# Patch-Prop.net
KiCad netlist of a schematic drawn in EAGLE
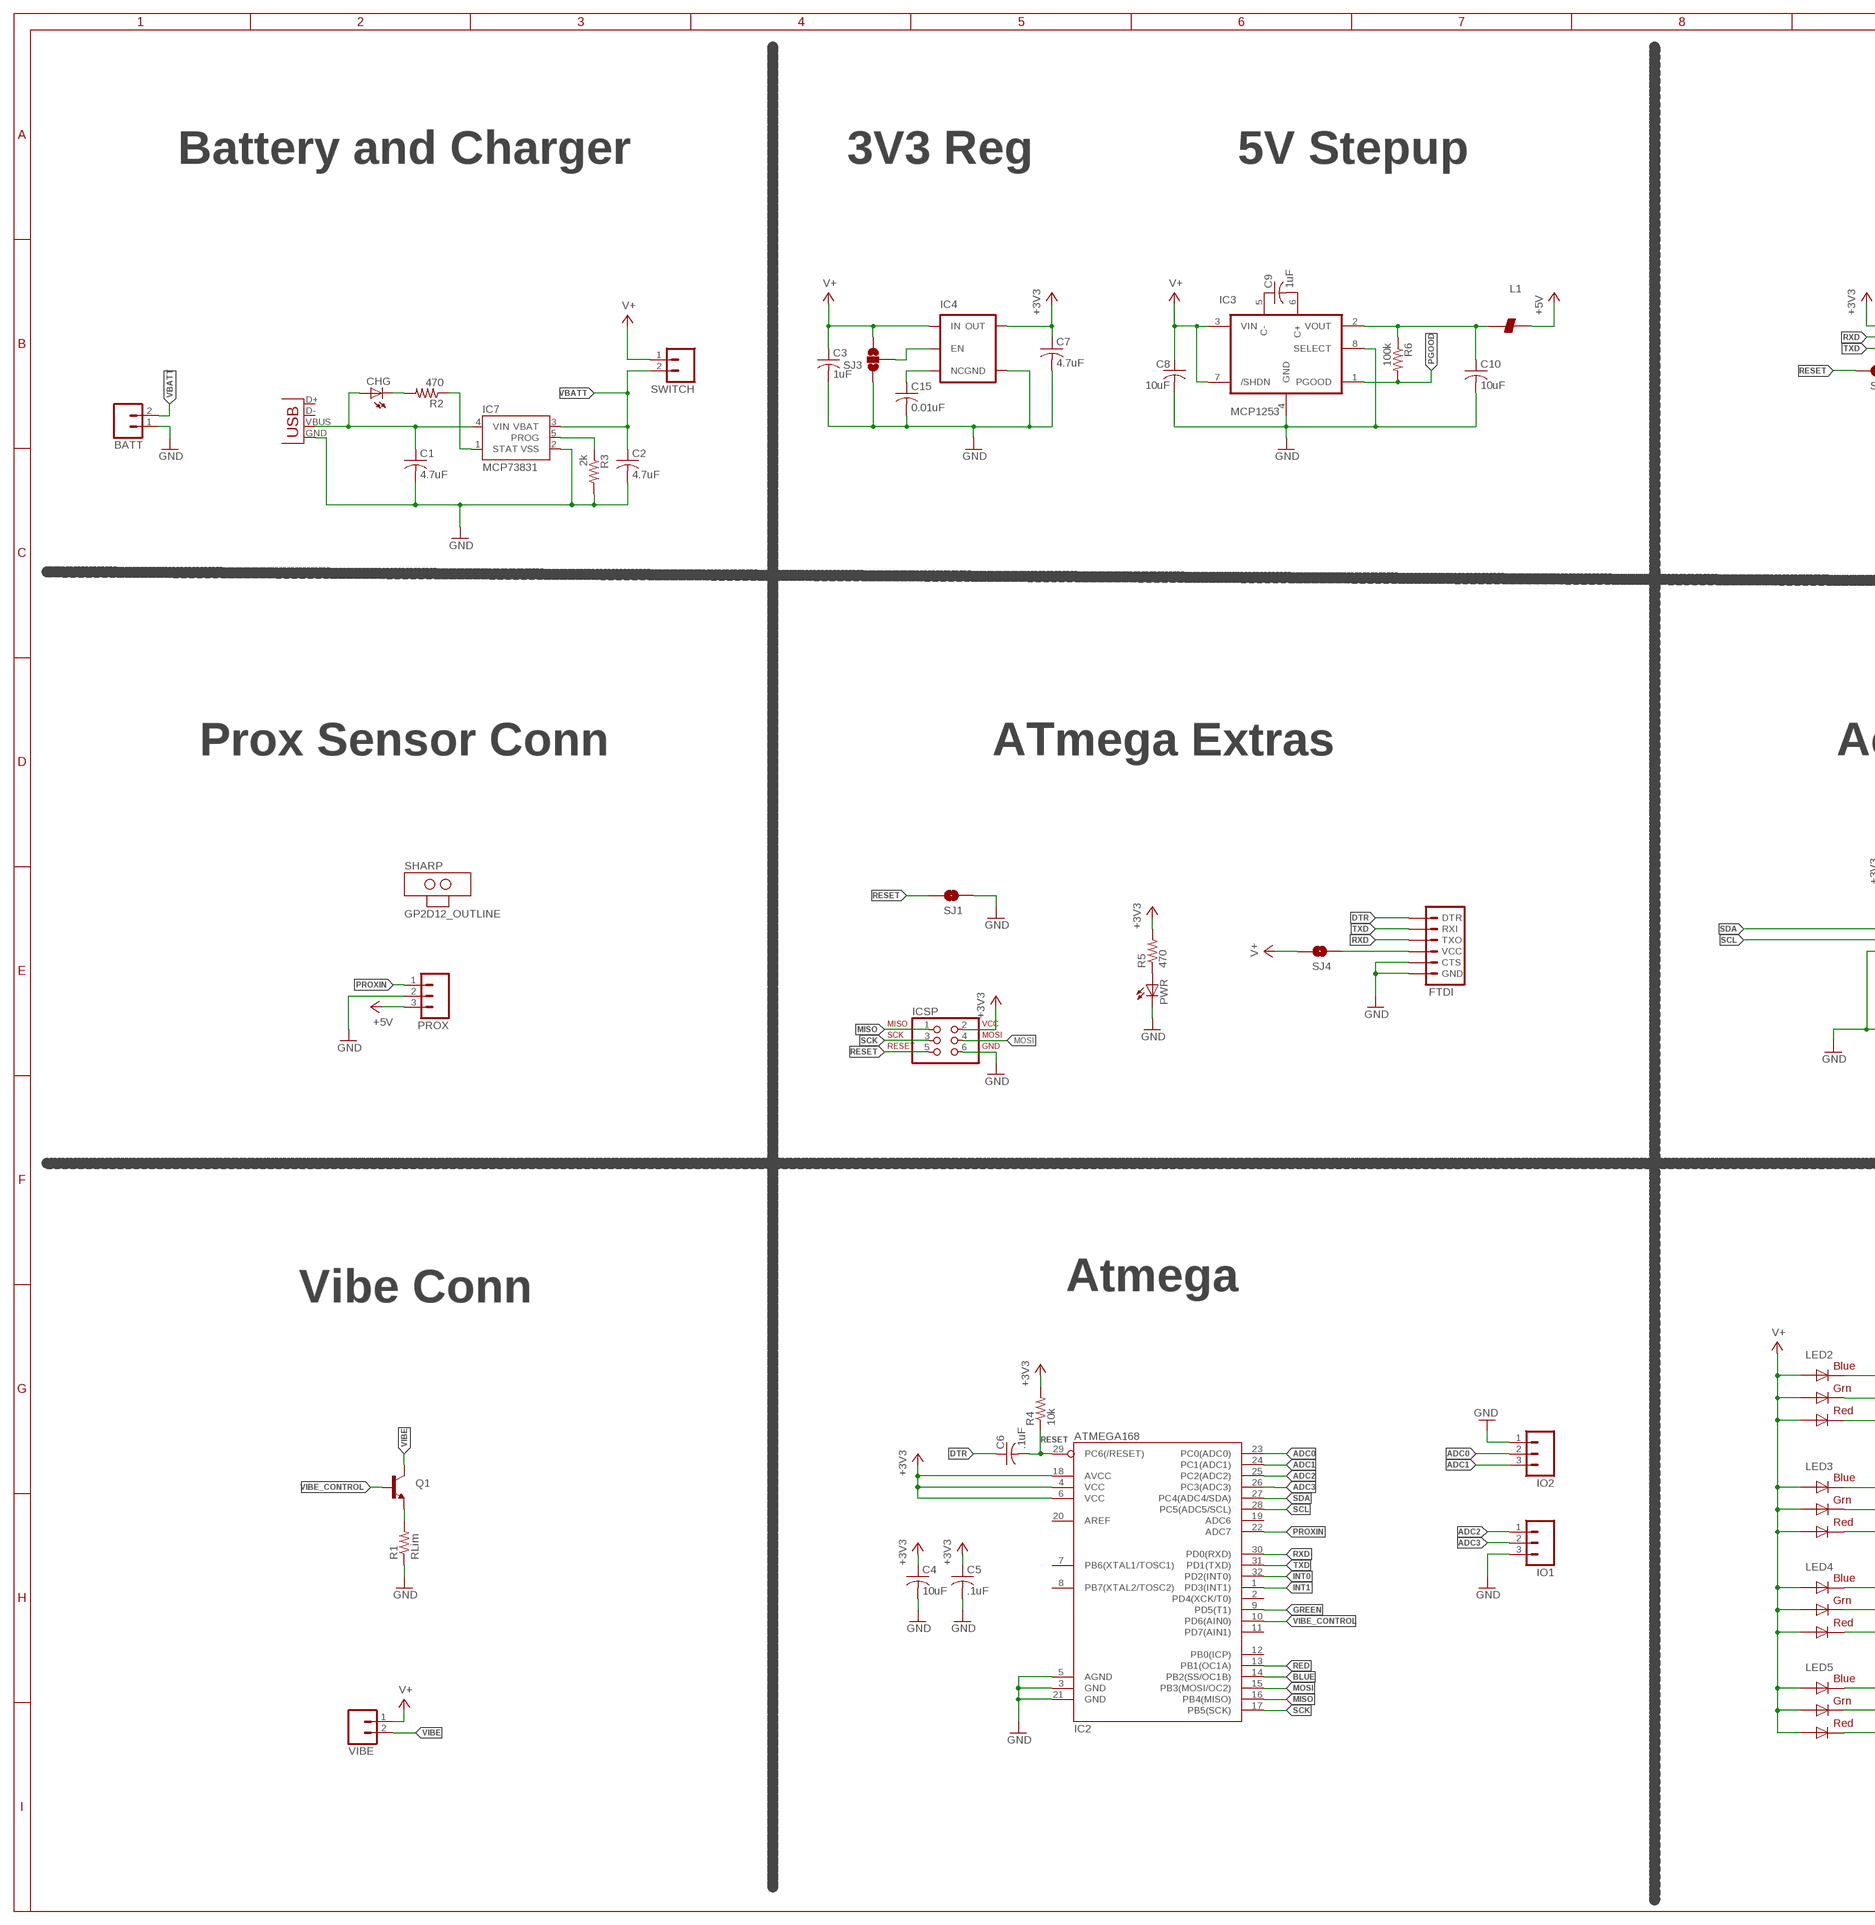
[diagram p0: schematic, sheet 1, part 1 of 2]
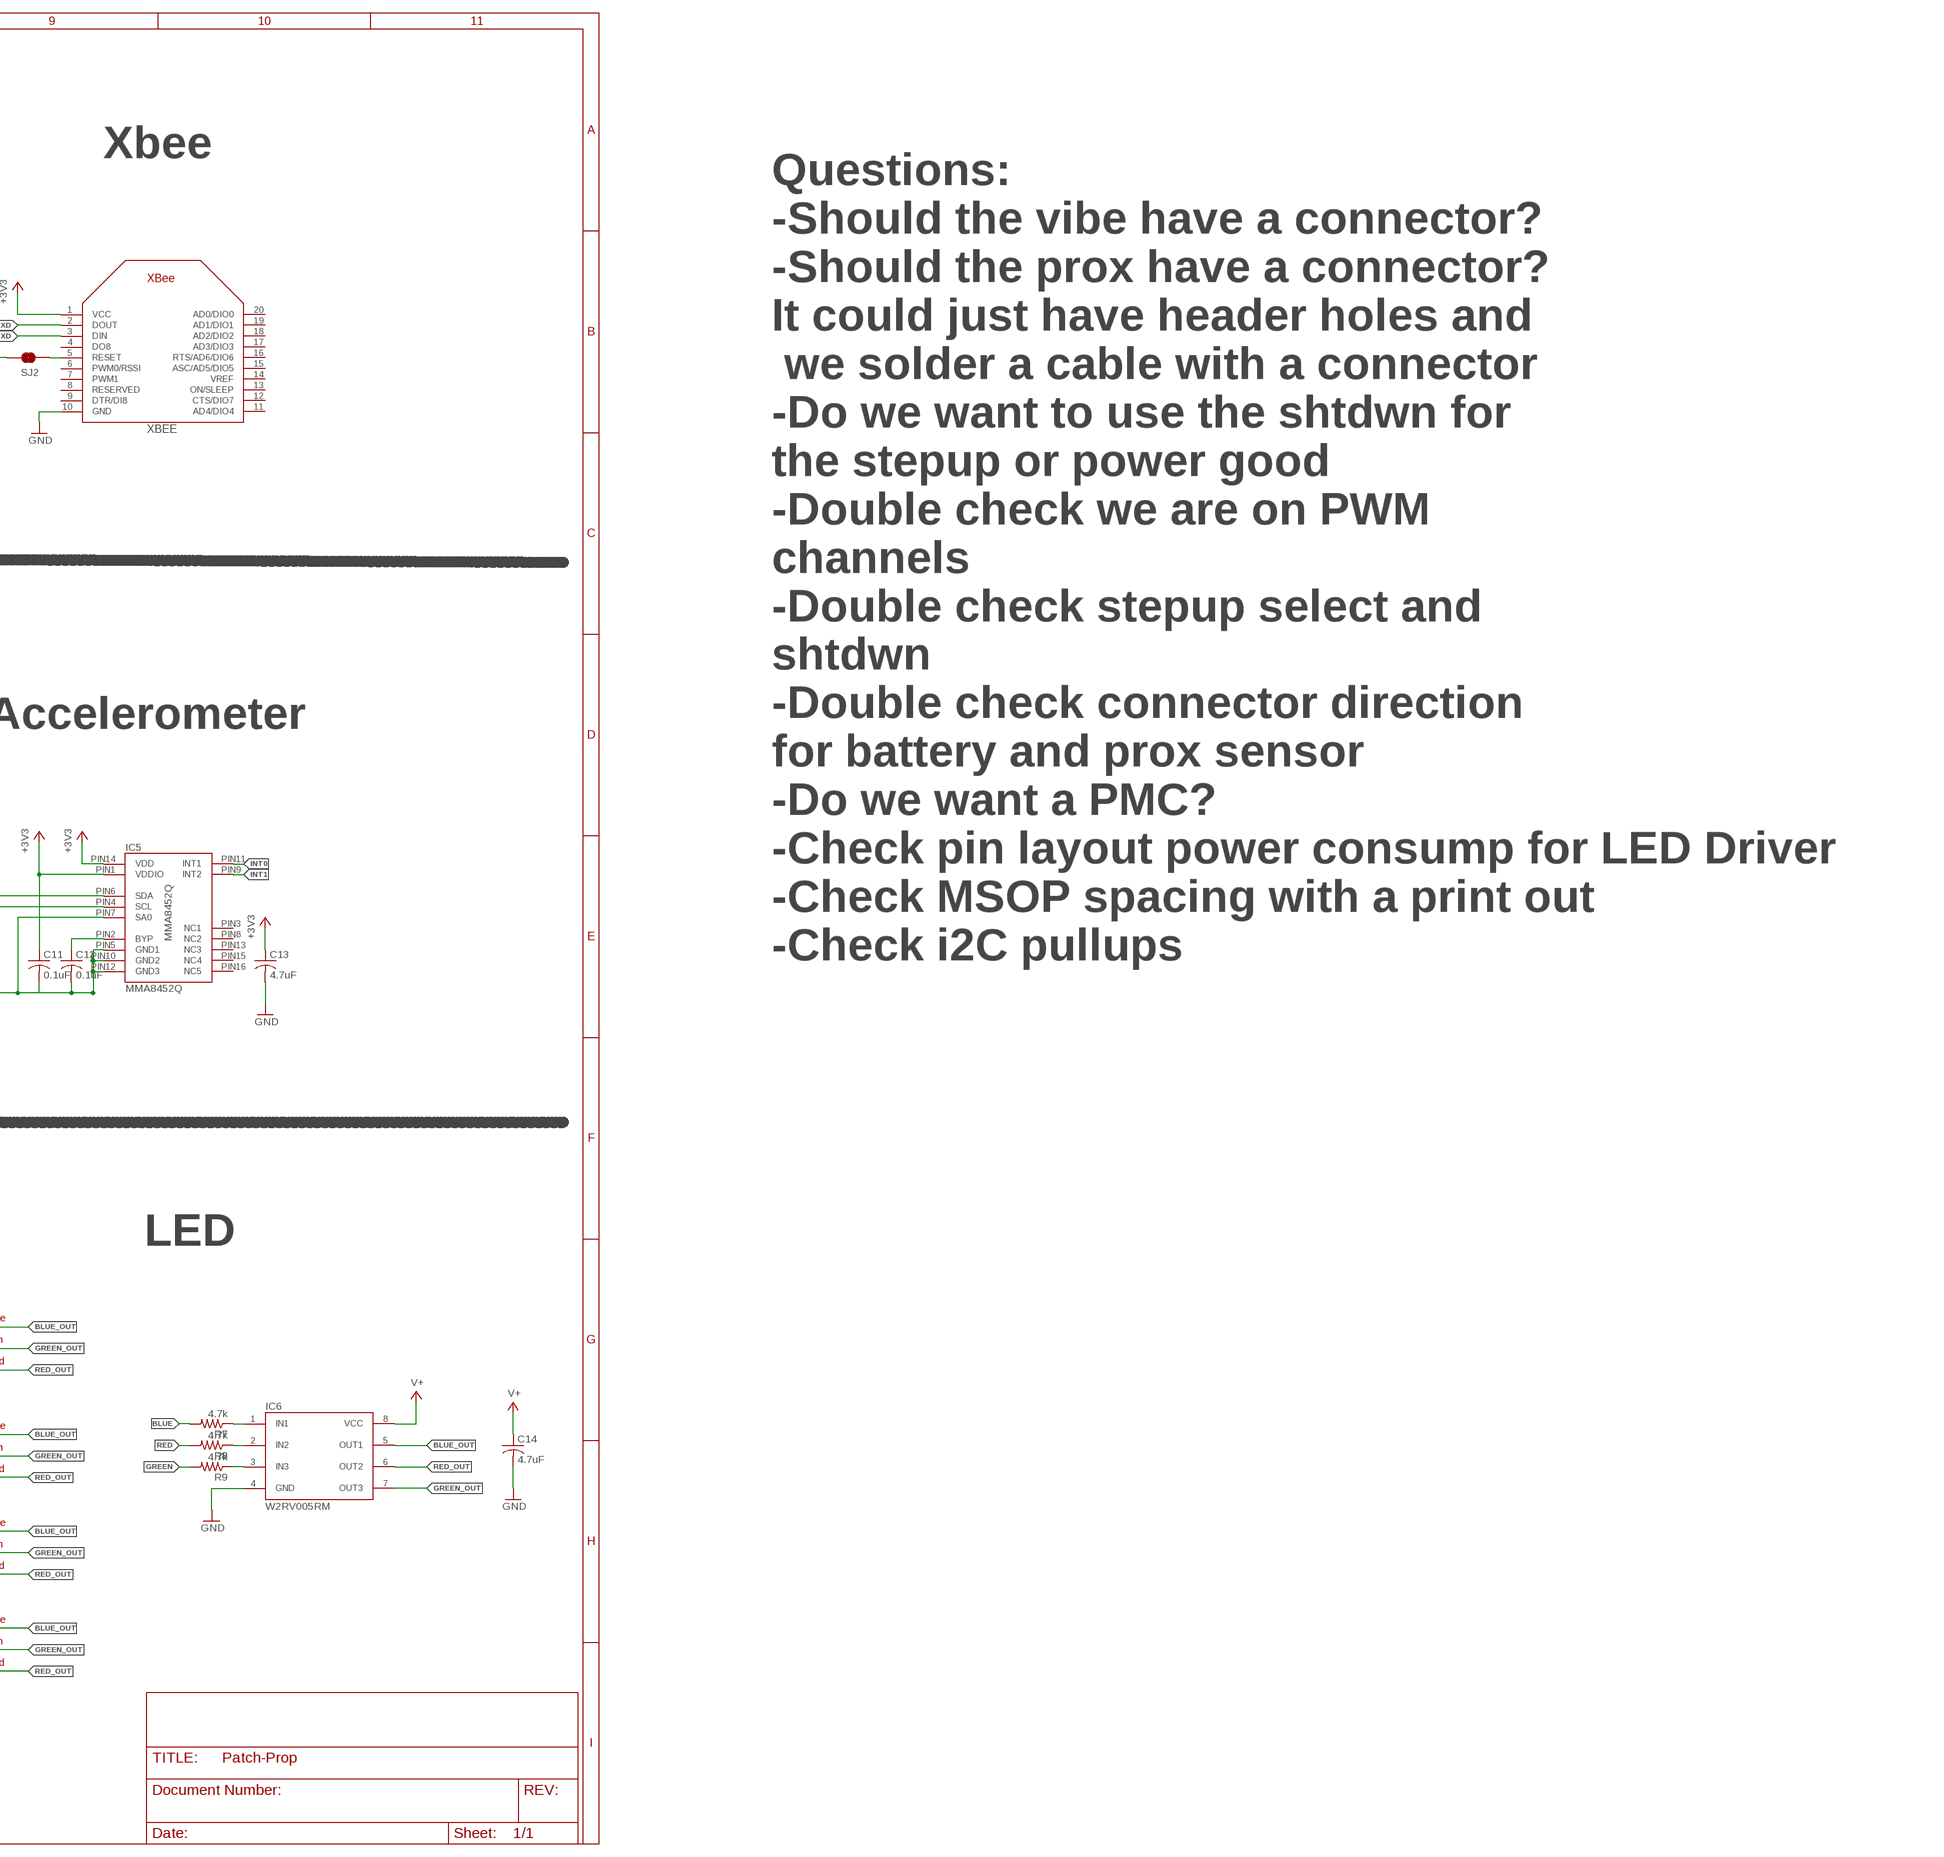
[diagram p1: schematic, sheet 1, part 2 of 2]

(export (version "E")
  (design (tool "Eeschema 10.0.6"))
  (components
    (comp (ref "BATT")
      (value "M02-JST-2MM-SMT")
      (footprint "eagle-import:JST-2-SMD")
      (libsource (lib "eagle-import") (part "SparkFun-Connectors_M02-JST-2MM-SMT"))
    )
    (comp (ref "C1")
      (value "4.7uF")
      (footprint "eagle-import:C0603")
      (libsource (lib "eagle-import") (part "C-USC0603"))
    )
    (comp (ref "C2")
      (value "4.7uF")
      (footprint "eagle-import:C0603")
      (libsource (lib "eagle-import") (part "C-USC0603"))
    )
    (comp (ref "C3")
      (value "1uF")
      (footprint "eagle-import:C0603")
      (libsource (lib "eagle-import") (part "C-USC0603"))
    )
    (comp (ref "C4")
      (value "10uF")
      (footprint "eagle-import:C0603")
      (libsource (lib "eagle-import") (part "C-USC0603"))
    )
    (comp (ref "C5")
      (value ".1uF")
      (footprint "eagle-import:C0603")
      (libsource (lib "eagle-import") (part "C-USC0603"))
    )
    (comp (ref "C6")
      (value ".1uF")
      (footprint "eagle-import:C0603")
      (libsource (lib "eagle-import") (part "C-USC0603"))
    )
    (comp (ref "C7")
      (value "4.7uF")
      (footprint "eagle-import:C0603")
      (libsource (lib "eagle-import") (part "C-USC0603"))
    )
    (comp (ref "C8")
      (value "10uF")
      (footprint "eagle-import:C0603")
      (libsource (lib "eagle-import") (part "C-USC0603"))
    )
    (comp (ref "C9")
      (value "1uF")
      (footprint "eagle-import:C0603")
      (libsource (lib "eagle-import") (part "C-USC0603"))
    )
    (comp (ref "C10")
      (value "10uF")
      (footprint "eagle-import:C0603")
      (libsource (lib "eagle-import") (part "C-USC0603"))
    )
    (comp (ref "C11")
      (value "0.1uF")
      (footprint "eagle-import:C0603")
      (libsource (lib "eagle-import") (part "C-USC0603"))
    )
    (comp (ref "C12")
      (value "0.1uF")
      (footprint "eagle-import:C0603")
      (libsource (lib "eagle-import") (part "C-USC0603"))
    )
    (comp (ref "C13")
      (value "4.7uF")
      (footprint "eagle-import:C0603")
      (libsource (lib "eagle-import") (part "C-USC0603"))
    )
    (comp (ref "C14")
      (value "4.7uF")
      (footprint "eagle-import:C0603")
      (libsource (lib "eagle-import") (part "C-USC0603"))
    )
    (comp (ref "C15")
      (value "0.01uF")
      (footprint "eagle-import:C0603")
      (libsource (lib "eagle-import") (part "C-USC0603"))
    )
    (comp (ref "CHG")
      (value "LEDCHIPLED_0805")
      (footprint "eagle-import:CHIPLED_0805")
      (libsource (lib "eagle-import") (part "LEDCHIPLED_0805"))
    )
    (comp (ref "FTDI")
      (value "ARDUINO_SERIAL_PROGRAMPTH")
      (footprint "eagle-import:1X06")
      (libsource (lib "eagle-import") (part "ARDUINO_SERIAL_PROGRAMPTH"))
    )
    (comp (ref "IC2")
      (value "ATMEGA168")
      (footprint "eagle-import:TQFP32-08")
      (libsource (lib "eagle-import") (part "ATMEGA168"))
    )
    (comp (ref "IC3")
      (value "MCP1253")
      (footprint "eagle-import:MSOP8")
      (libsource (lib "eagle-import") (part "MCP1253"))
    )
    (comp (ref "IC4")
      (value "V_REG_TPS76433SOT23-5")
      (footprint "eagle-import:SOT23-5")
      (libsource (lib "eagle-import") (part "V_REG_TPS76433SOT23-5"))
    )
    (comp (ref "IC5")
      (value "MMA8452Q")
      (footprint "eagle-import:QFN-16")
      (libsource (lib "eagle-import") (part "MMA8452Q"))
    )
    (comp (ref "IC6")
      (value "W2RV005RM")
      (footprint "eagle-import:MSOP8")
      (libsource (lib "eagle-import") (part "W2RV005RM"))
    )
    (comp (ref "IC7")
      (value "MCP73831")
      (footprint "eagle-import:SOT23-5")
      (libsource (lib "eagle-import") (part "MCP73831SMD"))
    )
    (comp (ref "ICSP")
      (value "ISP-AVR910SMD")
      (footprint "eagle-import:2X03_BORDER")
      (libsource (lib "eagle-import") (part "ISP-AVR910SMD"))
    )
    (comp (ref "IO1")
      (value "M03PTH")
      (footprint "eagle-import:1X03")
      (libsource (lib "eagle-import") (part "M03PTH"))
    )
    (comp (ref "IO2")
      (value "M03PTH")
      (footprint "eagle-import:1X03")
      (libsource (lib "eagle-import") (part "M03PTH"))
    )
    (comp (ref "L1")
      (value "BEAD-0805")
      (footprint "eagle-import:0805")
      (libsource (lib "eagle-import") (part "BEAD-0805"))
    )
    (comp (ref "LED2")
      (value "RGBLED5050")
      (footprint "eagle-import:RGBLED5050")
      (libsource (lib "eagle-import") (part "RGBLED5050"))
    )
    (comp (ref "LED3")
      (value "RGBLED5050")
      (footprint "eagle-import:RGBLED5050")
      (libsource (lib "eagle-import") (part "RGBLED5050"))
    )
    (comp (ref "LED4")
      (value "RGBLED5050")
      (footprint "eagle-import:RGBLED5050")
      (libsource (lib "eagle-import") (part "RGBLED5050"))
    )
    (comp (ref "LED5")
      (value "RGBLED5050")
      (footprint "eagle-import:RGBLED5050")
      (libsource (lib "eagle-import") (part "RGBLED5050"))
    )
    (comp (ref "PROX")
      (value "M03PTH")
      (footprint "eagle-import:1X03")
      (libsource (lib "eagle-import") (part "SparkFun-Connectors_M03PTH"))
    )
    (comp (ref "PWR")
      (value "LEDCHIPLED_0805")
      (footprint "eagle-import:CHIPLED_0805")
      (libsource (lib "eagle-import") (part "LEDCHIPLED_0805"))
    )
    (comp (ref "Q1")
      (value "TRANSISTOR_NPNSOT23")
      (footprint "eagle-import:SOT23")
      (libsource (lib "eagle-import") (part "TRANSISTOR_NPNSOT23"))
    )
    (comp (ref "R1")
      (value "RLim")
      (footprint "eagle-import:R0603")
      (libsource (lib "eagle-import") (part "R-US_R0603"))
    )
    (comp (ref "R2")
      (value "470")
      (footprint "eagle-import:R0603")
      (libsource (lib "eagle-import") (part "R-US_R0603"))
    )
    (comp (ref "R3")
      (value "2k")
      (footprint "eagle-import:R0603")
      (libsource (lib "eagle-import") (part "R-US_R0603"))
    )
    (comp (ref "R4")
      (value "10k")
      (footprint "eagle-import:R0603")
      (libsource (lib "eagle-import") (part "R-US_R0603"))
    )
    (comp (ref "R5")
      (value "470")
      (footprint "eagle-import:R0603")
      (libsource (lib "eagle-import") (part "R-US_R0603"))
    )
    (comp (ref "R6")
      (value "100k")
      (footprint "eagle-import:R0603")
      (libsource (lib "eagle-import") (part "R-US_R0603"))
    )
    (comp (ref "R7")
      (value "4.7k")
      (footprint "eagle-import:R0603")
      (libsource (lib "eagle-import") (part "R-US_R0603"))
    )
    (comp (ref "R8")
      (value "4.7k")
      (footprint "eagle-import:R0603")
      (libsource (lib "eagle-import") (part "R-US_R0603"))
    )
    (comp (ref "R9")
      (value "4.7k")
      (footprint "eagle-import:R0603")
      (libsource (lib "eagle-import") (part "R-US_R0603"))
    )
    (comp (ref "SHARP")
      (value "GP2D12_OUTLINE")
      (footprint "eagle-import:GP2D12_OUTLINE")
      (libsource (lib "eagle-import") (part "GP2D12_OUTLINE"))
    )
    (comp (ref "SJ1")
      (value "SOLDERJUMPERNO")
      (footprint "eagle-import:SJ_2S-NO")
      (libsource (lib "eagle-import") (part "SOLDERJUMPERNO"))
    )
    (comp (ref "SJ2")
      (value "SOLDERJUMPERNO")
      (footprint "eagle-import:SJ_2S-NO")
      (libsource (lib "eagle-import") (part "SOLDERJUMPERNO"))
    )
    (comp (ref "SJ3")
      (value "SOLDERJUMPER_2WAYS")
      (footprint "eagle-import:SJ_3")
      (libsource (lib "eagle-import") (part "SOLDERJUMPER_2WAYS"))
    )
    (comp (ref "SJ4")
      (value "SOLDERJUMPERNO")
      (footprint "eagle-import:SJ_2S-NO")
      (libsource (lib "eagle-import") (part "SOLDERJUMPERNO"))
    )
    (comp (ref "SWITCH")
      (value "M02PTH")
      (footprint "eagle-import:1X02")
      (libsource (lib "eagle-import") (part "M02PTH"))
    )
    (comp (ref "USB")
      (value "USBSMD")
      (footprint "eagle-import:USB-MINIB")
      (libsource (lib "eagle-import") (part "USBSMD"))
    )
    (comp (ref "VIBE")
      (value "M02PTH")
      (footprint "eagle-import:1X02")
      (libsource (lib "eagle-import") (part "SparkFun-Connectors_M02PTH"))
    )
    (comp (ref "XBEE")
      (value "XBEE")
      (footprint "eagle-import:XBEE")
      (libsource (lib "eagle-import") (part "XBEE"))
    )
  )
  (nets
    (net (code "1") (name "+3V3") (class "Default")
      (node (ref "C11") (pin "1") (pinfunction "1_1") (pintype "passive"))
      (node (ref "C13") (pin "1") (pinfunction "1_1") (pintype "passive"))
      (node (ref "C4") (pin "1") (pinfunction "1_1") (pintype "passive"))
      (node (ref "C5") (pin "1") (pinfunction "1_1") (pintype "passive"))
      (node (ref "C7") (pin "1") (pinfunction "1_1") (pintype "passive"))
      (node (ref "IC2") (pin "18") (pinfunction "AVCC_18") (pintype "bidirectional"))
      (node (ref "IC2") (pin "4") (pinfunction "VCC_4") (pintype "bidirectional"))
      (node (ref "IC2") (pin "6") (pinfunction "VCC_6") (pintype "bidirectional"))
      (node (ref "IC4") (pin "5") (pinfunction "OUT_5") (pintype "passive"))
      (node (ref "IC5") (pin "PIN1") (pinfunction "VDDIO_PIN1") (pintype "bidirectional"))
      (node (ref "IC5") (pin "PIN14") (pinfunction "VDD_PIN14") (pintype "bidirectional"))
      (node (ref "ICSP") (pin "2") (pinfunction "2_2") (pintype "passive"))
      (node (ref "R4") (pin "2") (pinfunction "2_2") (pintype "passive"))
      (node (ref "R5") (pin "2") (pinfunction "2_2") (pintype "passive"))
      (node (ref "XBEE") (pin "1") (pinfunction "VCC_1") (pintype "power_in"))
    )
    (net (code "2") (name "+5V") (class "Default")
      (node (ref "L1") (pin "2") (pinfunction "P$2_2") (pintype "passive"))
      (node (ref "PROX") (pin "3") (pinfunction "3_3") (pintype "passive"))
    )
    (net (code "3") (name "ADC0") (class "Default")
      (node (ref "IC2") (pin "23") (pinfunction "PC0(ADC0)_23") (pintype "bidirectional"))
      (node (ref "IO2") (pin "2") (pinfunction "2_2") (pintype "passive"))
    )
    (net (code "4") (name "ADC1") (class "Default")
      (node (ref "IC2") (pin "24") (pinfunction "PC1(ADC1)_24") (pintype "bidirectional"))
      (node (ref "IO2") (pin "3") (pinfunction "3_3") (pintype "passive"))
    )
    (net (code "5") (name "ADC2") (class "Default")
      (node (ref "IC2") (pin "25") (pinfunction "PC2(ADC2)_25") (pintype "bidirectional"))
      (node (ref "IO1") (pin "1") (pinfunction "1_1") (pintype "passive"))
    )
    (net (code "6") (name "ADC3") (class "Default")
      (node (ref "IC2") (pin "26") (pinfunction "PC3(ADC3)_26") (pintype "bidirectional"))
      (node (ref "IO1") (pin "2") (pinfunction "2_2") (pintype "passive"))
    )
    (net (code "7") (name "BLUE") (class "Default")
      (node (ref "IC2") (pin "14") (pinfunction "PB2(SS/OC1B)_14") (pintype "bidirectional"))
      (node (ref "R7") (pin "2") (pinfunction "2_2") (pintype "passive"))
    )
    (net (code "8") (name "BLUE_OUT") (class "Default")
      (node (ref "IC6") (pin "5") (pinfunction "OUT1_5") (pintype "output"))
      (node (ref "LED2") (pin "4") (pinfunction "BLUE_C_4") (pintype "bidirectional"))
      (node (ref "LED3") (pin "4") (pinfunction "BLUE_C_4") (pintype "bidirectional"))
      (node (ref "LED4") (pin "4") (pinfunction "BLUE_C_4") (pintype "bidirectional"))
      (node (ref "LED5") (pin "4") (pinfunction "BLUE_C_4") (pintype "bidirectional"))
    )
    (net (code "9") (name "DTR") (class "Default")
      (node (ref "C6") (pin "1") (pinfunction "1_1") (pintype "passive"))
      (node (ref "FTDI") (pin "1") (pinfunction "DTR_1") (pintype "passive"))
    )
    (net (code "10") (name "GND") (class "Default")
      (node (ref "BATT") (pin "1") (pinfunction "2_1") (pintype "passive"))
      (node (ref "C1") (pin "2") (pinfunction "2_2") (pintype "passive"))
      (node (ref "C10") (pin "2") (pinfunction "2_2") (pintype "passive"))
      (node (ref "C11") (pin "2") (pinfunction "2_2") (pintype "passive"))
      (node (ref "C12") (pin "2") (pinfunction "2_2") (pintype "passive"))
      (node (ref "C13") (pin "2") (pinfunction "2_2") (pintype "passive"))
      (node (ref "C14") (pin "2") (pinfunction "2_2") (pintype "passive"))
      (node (ref "C15") (pin "2") (pinfunction "2_2") (pintype "passive"))
      (node (ref "C2") (pin "2") (pinfunction "2_2") (pintype "passive"))
      (node (ref "C3") (pin "2") (pinfunction "2_2") (pintype "passive"))
      (node (ref "C4") (pin "2") (pinfunction "2_2") (pintype "passive"))
      (node (ref "C5") (pin "2") (pinfunction "2_2") (pintype "passive"))
      (node (ref "C7") (pin "2") (pinfunction "2_2") (pintype "passive"))
      (node (ref "C8") (pin "2") (pinfunction "2_2") (pintype "passive"))
      (node (ref "FTDI") (pin "5") (pinfunction "CTS_5") (pintype "passive"))
      (node (ref "FTDI") (pin "6") (pinfunction "GND_6") (pintype "passive"))
      (node (ref "IC2") (pin "21") (pinfunction "GND_21") (pintype "bidirectional"))
      (node (ref "IC2") (pin "3") (pinfunction "GND_3") (pintype "bidirectional"))
      (node (ref "IC2") (pin "5") (pinfunction "AGND_5") (pintype "bidirectional"))
      (node (ref "IC3") (pin "4") (pinfunction "GND_4") (pintype "bidirectional"))
      (node (ref "IC3") (pin "8") (pinfunction "SELECT_8") (pintype "bidirectional"))
      (node (ref "IC4") (pin "2") (pinfunction "GND_2") (pintype "input"))
      (node (ref "IC5") (pin "PIN10") (pinfunction "GND2_PIN10") (pintype "bidirectional"))
      (node (ref "IC5") (pin "PIN12") (pinfunction "GND3_PIN12") (pintype "bidirectional"))
      (node (ref "IC5") (pin "PIN5") (pinfunction "GND1_PIN5") (pintype "bidirectional"))
      (node (ref "IC5") (pin "PIN7") (pinfunction "SA0_PIN7") (pintype "bidirectional"))
      (node (ref "IC6") (pin "4") (pinfunction "GND_4") (pintype "bidirectional"))
      (node (ref "IC7") (pin "2") (pinfunction "VSS_2") (pintype "power_in"))
      (node (ref "ICSP") (pin "6") (pinfunction "6_6") (pintype "passive"))
      (node (ref "IO1") (pin "3") (pinfunction "3_3") (pintype "passive"))
      (node (ref "IO2") (pin "1") (pinfunction "1_1") (pintype "passive"))
      (node (ref "PROX") (pin "2") (pinfunction "2_2") (pintype "passive"))
      (node (ref "PWR") (pin "C") (pinfunction "C_C") (pintype "passive"))
      (node (ref "R1") (pin "1") (pinfunction "1_1") (pintype "passive"))
      (node (ref "R3") (pin "2") (pinfunction "2_2") (pintype "passive"))
      (node (ref "SJ1") (pin "1") (pinfunction "1_1") (pintype "passive"))
      (node (ref "SJ3") (pin "1") (pinfunction "1_1") (pintype "passive"))
      (node (ref "USB") (pin "GND") (pinfunction "GND_GND") (pintype "bidirectional"))
      (node (ref "XBEE") (pin "10") (pinfunction "GND_10") (pintype "power_in"))
    )
    (net (code "11") (name "GREEN") (class "Default")
      (node (ref "IC2") (pin "9") (pinfunction "PD5(T1)_9") (pintype "bidirectional"))
      (node (ref "R9") (pin "2") (pinfunction "2_2") (pintype "passive"))
    )
    (net (code "12") (name "GREEN_OUT") (class "Default")
      (node (ref "IC6") (pin "7") (pinfunction "OUT3_7") (pintype "output"))
      (node (ref "LED2") (pin "6") (pinfunction "GREEN_C_6") (pintype "bidirectional"))
      (node (ref "LED3") (pin "6") (pinfunction "GREEN_C_6") (pintype "bidirectional"))
      (node (ref "LED4") (pin "6") (pinfunction "GREEN_C_6") (pintype "bidirectional"))
      (node (ref "LED5") (pin "6") (pinfunction "GREEN_C_6") (pintype "bidirectional"))
    )
    (net (code "13") (name "INT0") (class "Default")
      (node (ref "IC2") (pin "32") (pinfunction "PD2(INT0)_32") (pintype "bidirectional"))
      (node (ref "IC5") (pin "PIN11") (pinfunction "INT1_PIN11") (pintype "bidirectional"))
    )
    (net (code "14") (name "INT1") (class "Default")
      (node (ref "IC2") (pin "1") (pinfunction "PD3(INT1)_1") (pintype "bidirectional"))
      (node (ref "IC5") (pin "PIN9") (pinfunction "INT2_PIN9") (pintype "bidirectional"))
    )
    (net (code "15") (name "MISO") (class "Default")
      (node (ref "IC2") (pin "16") (pinfunction "PB4(MISO)_16") (pintype "bidirectional"))
      (node (ref "ICSP") (pin "1") (pinfunction "1_1") (pintype "passive"))
    )
    (net (code "16") (name "MOSI") (class "Default")
      (node (ref "IC2") (pin "15") (pinfunction "PB3(MOSI/OC2)_15") (pintype "bidirectional"))
      (node (ref "ICSP") (pin "4") (pinfunction "4_4") (pintype "passive"))
    )
    (net (code "17") (name "Net-(CHG-PadC)") (class "Default")
      (node (ref "CHG") (pin "C") (pinfunction "C_C") (pintype "passive"))
      (node (ref "R2") (pin "2") (pinfunction "2_2") (pintype "passive"))
    )
    (net (code "18") (name "Net-(FTDI-VCC)") (class "Default")
      (node (ref "FTDI") (pin "4") (pinfunction "VCC_4") (pintype "passive"))
      (node (ref "SJ4") (pin "1") (pinfunction "1_1") (pintype "passive"))
    )
    (net (code "19") (name "Net-(IC3-C+)") (class "Default")
      (node (ref "C9") (pin "2") (pinfunction "2_2") (pintype "passive"))
      (node (ref "IC3") (pin "6") (pinfunction "C+_6") (pintype "bidirectional"))
    )
    (net (code "20") (name "Net-(IC3-C-)") (class "Default")
      (node (ref "C9") (pin "1") (pinfunction "1_1") (pintype "passive"))
      (node (ref "IC3") (pin "5") (pinfunction "C-_5") (pintype "bidirectional"))
    )
    (net (code "21") (name "Net-(IC3-VOUT)") (class "Default")
      (node (ref "C10") (pin "1") (pinfunction "1_1") (pintype "passive"))
      (node (ref "IC3") (pin "2") (pinfunction "VOUT_2") (pintype "bidirectional"))
      (node (ref "L1") (pin "1") (pinfunction "P$1_1") (pintype "passive"))
      (node (ref "R6") (pin "1") (pinfunction "1_1") (pintype "passive"))
    )
    (net (code "22") (name "Net-(IC4-EN)") (class "Default")
      (node (ref "IC4") (pin "3") (pinfunction "EN_3") (pintype "input"))
      (node (ref "SJ3") (pin "2") (pinfunction "2_2") (pintype "passive"))
    )
    (net (code "23") (name "Net-(IC4-NC)") (class "Default")
      (node (ref "C15") (pin "1") (pinfunction "1_1") (pintype "passive"))
      (node (ref "IC4") (pin "4") (pinfunction "NC_4") (pintype "input"))
    )
    (net (code "24") (name "Net-(IC5-BYP)") (class "Default")
      (node (ref "C12") (pin "1") (pinfunction "1_1") (pintype "passive"))
      (node (ref "IC5") (pin "PIN2") (pinfunction "BYP_PIN2") (pintype "bidirectional"))
    )
    (net (code "25") (name "Net-(IC6-IN1)") (class "Default")
      (node (ref "IC6") (pin "1") (pinfunction "IN1_1") (pintype "input"))
      (node (ref "R7") (pin "1") (pinfunction "1_1") (pintype "passive"))
    )
    (net (code "26") (name "Net-(IC6-IN2)") (class "Default")
      (node (ref "IC6") (pin "2") (pinfunction "IN2_2") (pintype "input"))
      (node (ref "R8") (pin "1") (pinfunction "1_1") (pintype "passive"))
    )
    (net (code "27") (name "Net-(IC6-IN3)") (class "Default")
      (node (ref "IC6") (pin "3") (pinfunction "IN3_3") (pintype "input"))
      (node (ref "R9") (pin "1") (pinfunction "1_1") (pintype "passive"))
    )
    (net (code "28") (name "Net-(IC7-PROG)") (class "Default")
      (node (ref "IC7") (pin "5") (pinfunction "PROG_5") (pintype "input"))
      (node (ref "R3") (pin "1") (pinfunction "1_1") (pintype "passive"))
    )
    (net (code "29") (name "Net-(IC7-STAT)") (class "Default")
      (node (ref "IC7") (pin "1") (pinfunction "STAT_1") (pintype "output"))
      (node (ref "R2") (pin "1") (pinfunction "1_1") (pintype "passive"))
    )
    (net (code "30") (name "Net-(IC7-VIN)") (class "Default")
      (node (ref "C1") (pin "1") (pinfunction "1_1") (pintype "passive"))
      (node (ref "CHG") (pin "A") (pinfunction "A_A") (pintype "passive"))
      (node (ref "IC7") (pin "4") (pinfunction "VIN_4") (pintype "power_in"))
      (node (ref "USB") (pin "VBUS") (pinfunction "VBUS_VBUS") (pintype "bidirectional"))
    )
    (net (code "31") (name "Net-(PWR-PadA)") (class "Default")
      (node (ref "PWR") (pin "A") (pinfunction "A_A") (pintype "passive"))
      (node (ref "R5") (pin "1") (pinfunction "1_1") (pintype "passive"))
    )
    (net (code "32") (name "Net-(Q1-E)") (class "Default")
      (node (ref "Q1") (pin "2") (pinfunction "E_2") (pintype "passive"))
      (node (ref "R1") (pin "2") (pinfunction "2_2") (pintype "passive"))
    )
    (net (code "33") (name "Net-(XBEE-RESET)") (class "Default")
      (node (ref "SJ2") (pin "1") (pinfunction "1_1") (pintype "passive"))
      (node (ref "XBEE") (pin "5") (pinfunction "RESET_5") (pintype "input"))
    )
    (net (code "34") (name "PGOOD") (class "Default")
      (node (ref "IC3") (pin "1") (pinfunction "PGOOD_1") (pintype "bidirectional"))
      (node (ref "R6") (pin "2") (pinfunction "2_2") (pintype "passive"))
    )
    (net (code "35") (name "PROXIN") (class "Default")
      (node (ref "IC2") (pin "22") (pinfunction "ADC7_22") (pintype "bidirectional"))
      (node (ref "PROX") (pin "1") (pinfunction "1_1") (pintype "passive"))
    )
    (net (code "36") (name "RED") (class "Default")
      (node (ref "IC2") (pin "13") (pinfunction "PB1(OC1A)_13") (pintype "bidirectional"))
      (node (ref "R8") (pin "2") (pinfunction "2_2") (pintype "passive"))
    )
    (net (code "37") (name "RED_OUT") (class "Default")
      (node (ref "IC6") (pin "6") (pinfunction "OUT2_6") (pintype "output"))
      (node (ref "LED2") (pin "5") (pinfunction "RED_C_5") (pintype "bidirectional"))
      (node (ref "LED3") (pin "5") (pinfunction "RED_C_5") (pintype "bidirectional"))
      (node (ref "LED4") (pin "5") (pinfunction "RED_C_5") (pintype "bidirectional"))
      (node (ref "LED5") (pin "5") (pinfunction "RED_C_5") (pintype "bidirectional"))
    )
    (net (code "38") (name "RESET") (class "Default")
      (node (ref "C6") (pin "2") (pinfunction "2_2") (pintype "passive"))
      (node (ref "IC2") (pin "29") (pinfunction "PC6(/RESET)_29") (pintype "bidirectional"))
      (node (ref "ICSP") (pin "5") (pinfunction "5_5") (pintype "passive"))
      (node (ref "R4") (pin "1") (pinfunction "1_1") (pintype "passive"))
      (node (ref "SJ1") (pin "2") (pinfunction "2_2") (pintype "passive"))
      (node (ref "SJ2") (pin "2") (pinfunction "2_2") (pintype "passive"))
    )
    (net (code "39") (name "RXD") (class "Default")
      (node (ref "FTDI") (pin "3") (pinfunction "TXO_3") (pintype "passive"))
      (node (ref "IC2") (pin "30") (pinfunction "PD0(RXD)_30") (pintype "bidirectional"))
      (node (ref "XBEE") (pin "2") (pinfunction "DOUT_2") (pintype "output"))
    )
    (net (code "40") (name "SCK") (class "Default")
      (node (ref "IC2") (pin "17") (pinfunction "PB5(SCK)_17") (pintype "bidirectional"))
      (node (ref "ICSP") (pin "3") (pinfunction "3_3") (pintype "passive"))
    )
    (net (code "41") (name "SCL") (class "Default")
      (node (ref "IC2") (pin "28") (pinfunction "PC5(ADC5/SCL)_28") (pintype "bidirectional"))
      (node (ref "IC5") (pin "PIN4") (pinfunction "SCL_PIN4") (pintype "bidirectional"))
    )
    (net (code "42") (name "SDA") (class "Default")
      (node (ref "IC2") (pin "27") (pinfunction "PC4(ADC4/SDA)_27") (pintype "bidirectional"))
      (node (ref "IC5") (pin "PIN6") (pinfunction "SDA_PIN6") (pintype "bidirectional"))
    )
    (net (code "43") (name "TXD") (class "Default")
      (node (ref "FTDI") (pin "2") (pinfunction "RXI_2") (pintype "passive"))
      (node (ref "IC2") (pin "31") (pinfunction "PD1(TXD)_31") (pintype "bidirectional"))
      (node (ref "XBEE") (pin "3") (pinfunction "DIN_3") (pintype "input"))
    )
    (net (code "44") (name "V+") (class "Default")
      (node (ref "C14") (pin "1") (pinfunction "1_1") (pintype "passive"))
      (node (ref "C3") (pin "1") (pinfunction "1_1") (pintype "passive"))
      (node (ref "C8") (pin "1") (pinfunction "1_1") (pintype "passive"))
      (node (ref "IC3") (pin "3") (pinfunction "VIN_3") (pintype "bidirectional"))
      (node (ref "IC3") (pin "7") (pinfunction "/SHDN_7") (pintype "bidirectional"))
      (node (ref "IC4") (pin "1") (pinfunction "IN_1") (pintype "input"))
      (node (ref "IC6") (pin "8") (pinfunction "VCC_8") (pintype "bidirectional"))
      (node (ref "LED2") (pin "1") (pinfunction "GREEN_A_1") (pintype "bidirectional"))
      (node (ref "LED2") (pin "2") (pinfunction "RED_A_2") (pintype "bidirectional"))
      (node (ref "LED2") (pin "3") (pinfunction "BLUE_A_3") (pintype "bidirectional"))
      (node (ref "LED3") (pin "1") (pinfunction "GREEN_A_1") (pintype "bidirectional"))
      (node (ref "LED3") (pin "2") (pinfunction "RED_A_2") (pintype "bidirectional"))
      (node (ref "LED3") (pin "3") (pinfunction "BLUE_A_3") (pintype "bidirectional"))
      (node (ref "LED4") (pin "1") (pinfunction "GREEN_A_1") (pintype "bidirectional"))
      (node (ref "LED4") (pin "2") (pinfunction "RED_A_2") (pintype "bidirectional"))
      (node (ref "LED4") (pin "3") (pinfunction "BLUE_A_3") (pintype "bidirectional"))
      (node (ref "LED5") (pin "1") (pinfunction "GREEN_A_1") (pintype "bidirectional"))
      (node (ref "LED5") (pin "2") (pinfunction "RED_A_2") (pintype "bidirectional"))
      (node (ref "LED5") (pin "3") (pinfunction "BLUE_A_3") (pintype "bidirectional"))
      (node (ref "SJ3") (pin "3") (pinfunction "3_3") (pintype "passive"))
      (node (ref "SJ4") (pin "2") (pinfunction "2_2") (pintype "passive"))
      (node (ref "SWITCH") (pin "1") (pinfunction "1_1") (pintype "passive"))
      (node (ref "VIBE") (pin "1") (pinfunction "1_1") (pintype "passive"))
    )
    (net (code "45") (name "VBATT") (class "Default")
      (node (ref "BATT") (pin "2") (pinfunction "1_2") (pintype "passive"))
      (node (ref "C2") (pin "1") (pinfunction "1_1") (pintype "passive"))
      (node (ref "IC7") (pin "3") (pinfunction "VBAT_3") (pintype "power_in"))
      (node (ref "SWITCH") (pin "2") (pinfunction "2_2") (pintype "passive"))
    )
    (net (code "46") (name "VIBE") (class "Default")
      (node (ref "Q1") (pin "3") (pinfunction "C_3") (pintype "passive"))
      (node (ref "VIBE") (pin "2") (pinfunction "2_2") (pintype "passive"))
    )
    (net (code "47") (name "VIBE_CONTROL") (class "Default")
      (node (ref "IC2") (pin "10") (pinfunction "PD6(AIN0)_10") (pintype "bidirectional"))
      (node (ref "Q1") (pin "1") (pinfunction "B_1") (pintype "passive"))
    )
    (net (code "48") (name "unconnected-(IC2-ADC6-Pad19)") (class "Default")
      (node (ref "IC2") (pin "19") (pinfunction "ADC6_19") (pintype "bidirectional"))
    )
    (net (code "49") (name "unconnected-(IC2-AREF-Pad20)") (class "Default")
      (node (ref "IC2") (pin "20") (pinfunction "AREF_20") (pintype "bidirectional"))
    )
    (net (code "50") (name "unconnected-(IC2-PB0(ICP)-Pad12)") (class "Default")
      (node (ref "IC2") (pin "12") (pinfunction "PB0(ICP)_12") (pintype "bidirectional"))
    )
    (net (code "51") (name "unconnected-(IC2-PB6(XTAL1{slash}TOSC1)-Pad7)") (class "Default")
      (node (ref "IC2") (pin "7") (pinfunction "PB6(XTAL1/TOSC1)_7") (pintype "bidirectional"))
    )
    (net (code "52") (name "unconnected-(IC2-PB7(XTAL2{slash}TOSC2)-Pad8)") (class "Default")
      (node (ref "IC2") (pin "8") (pinfunction "PB7(XTAL2/TOSC2)_8") (pintype "bidirectional"))
    )
    (net (code "53") (name "unconnected-(IC2-PD4(XCK{slash}T0)-Pad2)") (class "Default")
      (node (ref "IC2") (pin "2") (pinfunction "PD4(XCK/T0)_2") (pintype "bidirectional"))
    )
    (net (code "54") (name "unconnected-(IC2-PD7(AIN1)-Pad11)") (class "Default")
      (node (ref "IC2") (pin "11") (pinfunction "PD7(AIN1)_11") (pintype "bidirectional"))
    )
    (net (code "55") (name "unconnected-(IC5-NC1-PadPIN3)") (class "Default")
      (node (ref "IC5") (pin "PIN3") (pinfunction "NC1_PIN3") (pintype "bidirectional"))
    )
    (net (code "56") (name "unconnected-(IC5-NC2-PadPIN8)") (class "Default")
      (node (ref "IC5") (pin "PIN8") (pinfunction "NC2_PIN8") (pintype "bidirectional"))
    )
    (net (code "57") (name "unconnected-(IC5-NC3-PadPIN13)") (class "Default")
      (node (ref "IC5") (pin "PIN13") (pinfunction "NC3_PIN13") (pintype "bidirectional"))
    )
    (net (code "58") (name "unconnected-(IC5-NC4-PadPIN15)") (class "Default")
      (node (ref "IC5") (pin "PIN15") (pinfunction "NC4_PIN15") (pintype "bidirectional"))
    )
    (net (code "59") (name "unconnected-(IC5-NC5-PadPIN16)") (class "Default")
      (node (ref "IC5") (pin "PIN16") (pinfunction "NC5_PIN16") (pintype "bidirectional"))
    )
    (net (code "60") (name "unconnected-(USB-PadD+)") (class "Default")
      (node (ref "USB") (pin "D+") (pinfunction "D+_D+") (pintype "bidirectional"))
    )
    (net (code "61") (name "unconnected-(USB-PadD-)") (class "Default")
      (node (ref "USB") (pin "D-") (pinfunction "D-_D-") (pintype "bidirectional"))
    )
    (net (code "62") (name "unconnected-(XBEE-AD0{slash}DIO0-Pad20)") (class "Default")
      (node (ref "XBEE") (pin "20") (pinfunction "AD0/DIO0_20") (pintype "bidirectional"))
    )
    (net (code "63") (name "unconnected-(XBEE-AD1{slash}DIO1-Pad19)") (class "Default")
      (node (ref "XBEE") (pin "19") (pinfunction "AD1/DIO1_19") (pintype "bidirectional"))
    )
    (net (code "64") (name "unconnected-(XBEE-AD2{slash}DIO2-Pad18)") (class "Default")
      (node (ref "XBEE") (pin "18") (pinfunction "AD2/DIO2_18") (pintype "bidirectional"))
    )
    (net (code "65") (name "unconnected-(XBEE-AD3{slash}DIO3-Pad17)") (class "Default")
      (node (ref "XBEE") (pin "17") (pinfunction "AD3/DIO3_17") (pintype "bidirectional"))
    )
    (net (code "66") (name "unconnected-(XBEE-AD4{slash}DIO4-Pad11)") (class "Default")
      (node (ref "XBEE") (pin "11") (pinfunction "AD4/DIO4_11") (pintype "bidirectional"))
    )
    (net (code "67") (name "unconnected-(XBEE-ASC{slash}AD5{slash}DIO5-Pad15)") (class "Default")
      (node (ref "XBEE") (pin "15") (pinfunction "ASC/AD5/DIO5_15") (pintype "bidirectional"))
    )
    (net (code "68") (name "unconnected-(XBEE-CTS{slash}DIO7-Pad12)") (class "Default")
      (node (ref "XBEE") (pin "12") (pinfunction "CTS/DIO7_12") (pintype "bidirectional"))
    )
    (net (code "69") (name "unconnected-(XBEE-DO8-Pad4)") (class "Default")
      (node (ref "XBEE") (pin "4") (pinfunction "DO8_4") (pintype "output"))
    )
    (net (code "70") (name "unconnected-(XBEE-DTR{slash}DI8-Pad9)") (class "Default")
      (node (ref "XBEE") (pin "9") (pinfunction "DTR/DI8_9") (pintype "input"))
    )
    (net (code "71") (name "unconnected-(XBEE-ON{slash}SLEEP-Pad13)") (class "Default")
      (node (ref "XBEE") (pin "13") (pinfunction "ON/SLEEP_13") (pintype "output"))
    )
    (net (code "72") (name "unconnected-(XBEE-PWM0{slash}RSSI-Pad6)") (class "Default")
      (node (ref "XBEE") (pin "6") (pinfunction "PWM0/RSSI_6") (pintype "output"))
    )
    (net (code "73") (name "unconnected-(XBEE-PWM1-Pad7)") (class "Default")
      (node (ref "XBEE") (pin "7") (pinfunction "PWM1_7") (pintype "output"))
    )
    (net (code "74") (name "unconnected-(XBEE-RESERVED-Pad8)") (class "Default")
      (node (ref "XBEE") (pin "8") (pinfunction "RESERVED_8") (pintype "no_connect"))
    )
    (net (code "75") (name "unconnected-(XBEE-RTS{slash}AD6{slash}DIO6-Pad16)") (class "Default")
      (node (ref "XBEE") (pin "16") (pinfunction "RTS/AD6/DIO6_16") (pintype "bidirectional"))
    )
    (net (code "76") (name "unconnected-(XBEE-VREF-Pad14)") (class "Default")
      (node (ref "XBEE") (pin "14") (pinfunction "VREF_14") (pintype "input"))
    )
  )
)
